# BatManagement.net
KiCad netlist of a schematic drawn in EAGLE
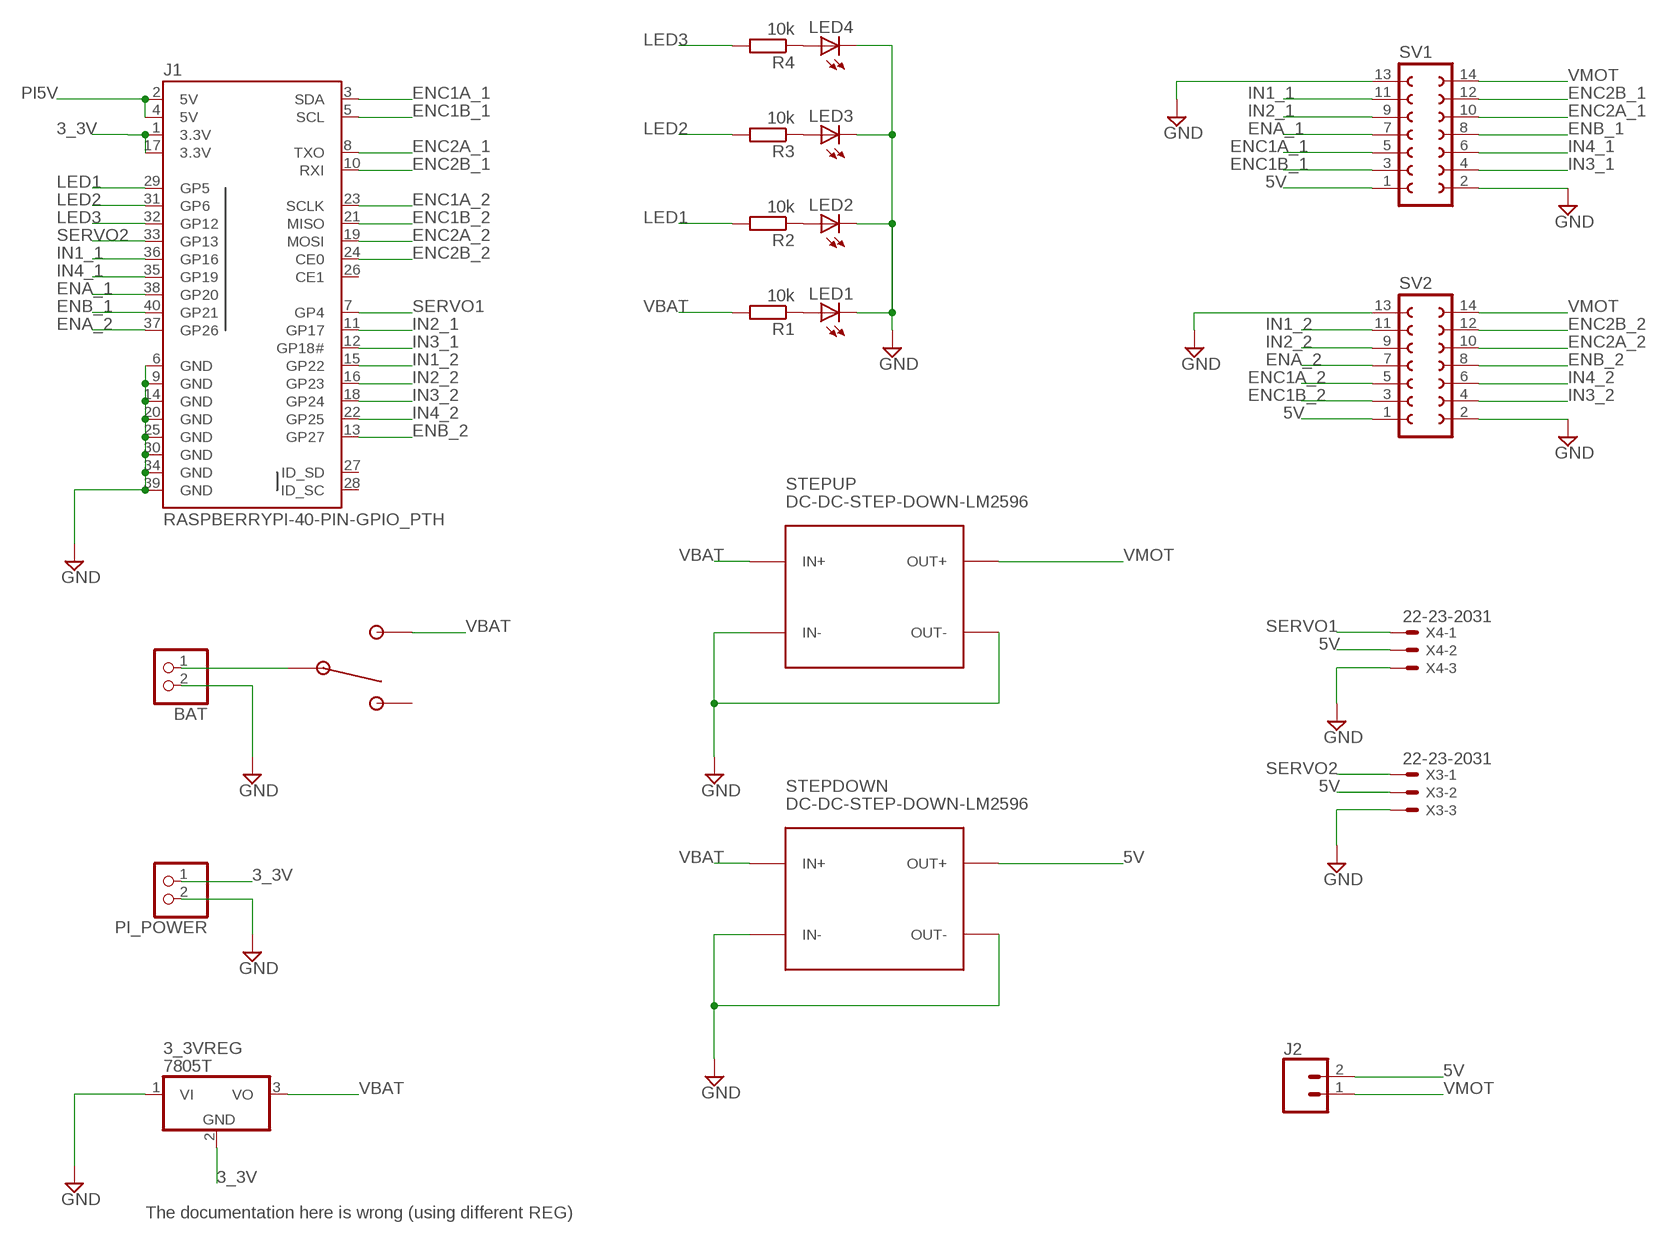
[diagram p0: schematic, sheet 1]

(export (version "E")
  (design (tool "Eeschema 10.0.6"))
  (components
    (comp (ref "3_3VREG")
      (value "7805T")
      (footprint "eagle-import:TO220H")
      (libsource (lib "eagle-import") (part "78T05"))
    )
    (comp (ref "BAT")
      (value "JST_2PIN-THM")
      (footprint "eagle-import:JST-PH-2-THM")
      (libsource (lib "eagle-import") (part "JST_2PIN-THM"))
    )
    (comp (ref "J1")
      (value "RASPBERRYPI-40-PIN-GPIO_PTH")
      (footprint "eagle-import:2X20_SHROUDED")
      (libsource (lib "eagle-import") (part "RASPBERRYPI-40-PIN-GPIO_PTH"))
    )
    (comp (ref "J2")
      (value "CONN_02")
      (footprint "eagle-import:1X02")
      (libsource (lib "eagle-import") (part "CONN_02"))
    )
    (comp (ref "LED1")
      (value "LED5MM")
      (footprint "eagle-import:LED5MM")
      (libsource (lib "eagle-import") (part "LED5MM"))
    )
    (comp (ref "LED2")
      (value "LED5MM")
      (footprint "eagle-import:LED5MM")
      (libsource (lib "eagle-import") (part "LED5MM"))
    )
    (comp (ref "LED3")
      (value "LED5MM")
      (footprint "eagle-import:LED5MM")
      (libsource (lib "eagle-import") (part "LED5MM"))
    )
    (comp (ref "LED4")
      (value "LED5MM")
      (footprint "eagle-import:LED5MM")
      (libsource (lib "eagle-import") (part "LED5MM"))
    )
    (comp (ref "PI_POWER")
      (value "JST_2PIN-THM")
      (footprint "eagle-import:JST-PH-2-THM")
      (libsource (lib "eagle-import") (part "JST_2PIN-THM"))
    )
    (comp (ref "R1")
      (value "10k")
      (footprint "eagle-import:0204_5")
      (libsource (lib "eagle-import") (part "R-EU_0204/5"))
    )
    (comp (ref "R2")
      (value "10k")
      (footprint "eagle-import:0204_5")
      (libsource (lib "eagle-import") (part "R-EU_0204/5"))
    )
    (comp (ref "R3")
      (value "10k")
      (footprint "eagle-import:0204_5")
      (libsource (lib "eagle-import") (part "R-EU_0204/5"))
    )
    (comp (ref "R4")
      (value "10k")
      (footprint "eagle-import:0204_5")
      (libsource (lib "eagle-import") (part "R-EU_0204/5"))
    )
    (comp (ref "STEPDOWN")
      (value "DC-DC-STEP-DOWN-LM2596")
      (footprint "eagle-import:DC-DC-STEP-DOWN-LM2596")
      (libsource (lib "eagle-import") (part "DC-DC-STEP-DOWN-LM2596"))
    )
    (comp (ref "STEPUP")
      (value "DC-DC-STEP-DOWN-LM2596")
      (footprint "eagle-import:DC-DC-STEP-DOWN-LM2596")
      (libsource (lib "eagle-import") (part "DC-DC-STEP-DOWN-LM2596"))
    )
    (comp (ref "SV1")
      (value "FE07-2")
      (footprint "eagle-import:FE07-2")
      (libsource (lib "eagle-import") (part "FE07-2"))
    )
    (comp (ref "SV2")
      (value "FE07-2")
      (footprint "eagle-import:FE07-2")
      (libsource (lib "eagle-import") (part "FE07-2"))
    )
    (comp (ref "SW1")
      (value "100SP1T2B4M6QE")
      (footprint "eagle-import:TOGGLE_RA")
      (fields (field (name "MF") "E-Switch"))
      (libsource (lib "eagle-import") (part "100SP1T2B4M6QE"))
    )
    (comp (ref "X3")
      (value "22-23-2031")
      (footprint "eagle-import:22-23-2031")
      (fields (field (name "MF") "MOLEX"))
      (libsource (lib "eagle-import") (part "22-23-2031"))
    )
    (comp (ref "X4")
      (value "22-23-2031")
      (footprint "eagle-import:22-23-2031")
      (fields (field (name "MF") "MOLEX"))
      (libsource (lib "eagle-import") (part "22-23-2031"))
    )
  )
  (nets
    (net (code "1") (name "/3_3V") (class "Default")
      (node (ref "3_3VREG") (pin "2") (pinfunction "GND_2") (pintype "passive"))
      (node (ref "J1") (pin "1") (pinfunction "3.3V_1") (pintype "power_in"))
      (node (ref "J1") (pin "17") (pinfunction "3.3V_17") (pintype "power_in"))
      (node (ref "PI_POWER") (pin "1") (pinfunction "2_1") (pintype "passive"))
    )
    (net (code "2") (name "/5V") (class "Default")
      (node (ref "J2") (pin "2") (pinfunction "2_2") (pintype "passive"))
      (node (ref "STEPDOWN") (pin "OUT+") (pinfunction "OUT+_OUT+") (pintype "bidirectional"))
      (node (ref "SV1") (pin "1") (pinfunction "1_1") (pintype "passive"))
      (node (ref "SV2") (pin "1") (pinfunction "1_1") (pintype "passive"))
      (node (ref "X3") (pin "2") (pinfunction "S_2") (pintype "passive"))
      (node (ref "X4") (pin "2") (pinfunction "S_2") (pintype "passive"))
    )
    (net (code "3") (name "/ENA_1") (class "Default")
      (node (ref "J1") (pin "38") (pinfunction "GP20_38") (pintype "bidirectional"))
      (node (ref "SV1") (pin "7") (pinfunction "7_7") (pintype "passive"))
    )
    (net (code "4") (name "/ENA_2") (class "Default")
      (node (ref "J1") (pin "37") (pinfunction "GP26_37") (pintype "bidirectional"))
      (node (ref "SV2") (pin "7") (pinfunction "7_7") (pintype "passive"))
    )
    (net (code "5") (name "/ENB_1") (class "Default")
      (node (ref "J1") (pin "40") (pinfunction "GP21_40") (pintype "bidirectional"))
      (node (ref "SV1") (pin "8") (pinfunction "8_8") (pintype "passive"))
    )
    (net (code "6") (name "/ENB_2") (class "Default")
      (node (ref "J1") (pin "13") (pinfunction "GP27_13") (pintype "bidirectional"))
      (node (ref "SV2") (pin "8") (pinfunction "8_8") (pintype "passive"))
    )
    (net (code "7") (name "/ENC1A_1") (class "Default")
      (node (ref "J1") (pin "3") (pinfunction "SDA_3") (pintype "bidirectional"))
      (node (ref "SV1") (pin "5") (pinfunction "5_5") (pintype "passive"))
    )
    (net (code "8") (name "/ENC1A_2") (class "Default")
      (node (ref "J1") (pin "23") (pinfunction "SCLK_23") (pintype "output"))
      (node (ref "SV2") (pin "5") (pinfunction "5_5") (pintype "passive"))
    )
    (net (code "9") (name "/ENC1B_1") (class "Default")
      (node (ref "J1") (pin "5") (pinfunction "SCL_5") (pintype "bidirectional"))
      (node (ref "SV1") (pin "3") (pinfunction "3_3") (pintype "passive"))
    )
    (net (code "10") (name "/ENC1B_2") (class "Default")
      (node (ref "J1") (pin "21") (pinfunction "MISO_21") (pintype "input"))
      (node (ref "SV2") (pin "3") (pinfunction "3_3") (pintype "passive"))
    )
    (net (code "11") (name "/ENC2A_1") (class "Default")
      (node (ref "J1") (pin "8") (pinfunction "TXO_8") (pintype "output"))
      (node (ref "SV1") (pin "10") (pinfunction "10_10") (pintype "passive"))
    )
    (net (code "12") (name "/ENC2A_2") (class "Default")
      (node (ref "J1") (pin "19") (pinfunction "MOSI_19") (pintype "output"))
      (node (ref "SV2") (pin "10") (pinfunction "10_10") (pintype "passive"))
    )
    (net (code "13") (name "/ENC2B_1") (class "Default")
      (node (ref "J1") (pin "10") (pinfunction "RXI_10") (pintype "input"))
      (node (ref "SV1") (pin "12") (pinfunction "12_12") (pintype "passive"))
    )
    (net (code "14") (name "/ENC2B_2") (class "Default")
      (node (ref "J1") (pin "24") (pinfunction "CE0_24") (pintype "output"))
      (node (ref "SV2") (pin "12") (pinfunction "12_12") (pintype "passive"))
    )
    (net (code "15") (name "/IN1_1") (class "Default")
      (node (ref "J1") (pin "36") (pinfunction "GP16_36") (pintype "bidirectional"))
      (node (ref "SV1") (pin "11") (pinfunction "11_11") (pintype "passive"))
    )
    (net (code "16") (name "/IN1_2") (class "Default")
      (node (ref "J1") (pin "15") (pinfunction "GP22_15") (pintype "bidirectional"))
      (node (ref "SV2") (pin "11") (pinfunction "11_11") (pintype "passive"))
    )
    (net (code "17") (name "/IN2_1") (class "Default")
      (node (ref "J1") (pin "11") (pinfunction "GP17_11") (pintype "bidirectional"))
      (node (ref "SV1") (pin "9") (pinfunction "9_9") (pintype "passive"))
    )
    (net (code "18") (name "/IN2_2") (class "Default")
      (node (ref "J1") (pin "16") (pinfunction "GP23_16") (pintype "bidirectional"))
      (node (ref "SV2") (pin "9") (pinfunction "9_9") (pintype "passive"))
    )
    (net (code "19") (name "/IN3_1") (class "Default")
      (node (ref "J1") (pin "12") (pinfunction "GP18#_12") (pintype "bidirectional"))
      (node (ref "SV1") (pin "4") (pinfunction "4_4") (pintype "passive"))
    )
    (net (code "20") (name "/IN3_2") (class "Default")
      (node (ref "J1") (pin "18") (pinfunction "GP24_18") (pintype "bidirectional"))
      (node (ref "SV2") (pin "4") (pinfunction "4_4") (pintype "passive"))
    )
    (net (code "21") (name "/IN4_1") (class "Default")
      (node (ref "J1") (pin "35") (pinfunction "GP19_35") (pintype "bidirectional"))
      (node (ref "SV1") (pin "6") (pinfunction "6_6") (pintype "passive"))
    )
    (net (code "22") (name "/IN4_2") (class "Default")
      (node (ref "J1") (pin "22") (pinfunction "GP25_22") (pintype "bidirectional"))
      (node (ref "SV2") (pin "6") (pinfunction "6_6") (pintype "passive"))
    )
    (net (code "23") (name "/LED1") (class "Default")
      (node (ref "J1") (pin "29") (pinfunction "GP5_29") (pintype "bidirectional"))
      (node (ref "R2") (pin "2") (pinfunction "2_2") (pintype "passive"))
    )
    (net (code "24") (name "/LED2") (class "Default")
      (node (ref "J1") (pin "31") (pinfunction "GP6_31") (pintype "bidirectional"))
      (node (ref "R3") (pin "2") (pinfunction "2_2") (pintype "passive"))
    )
    (net (code "25") (name "/LED3") (class "Default")
      (node (ref "J1") (pin "32") (pinfunction "GP12_32") (pintype "bidirectional"))
      (node (ref "R4") (pin "2") (pinfunction "2_2") (pintype "passive"))
    )
    (net (code "26") (name "/PI5V") (class "Default")
      (node (ref "J1") (pin "2") (pinfunction "5V_2") (pintype "power_in"))
      (node (ref "J1") (pin "4") (pinfunction "5V_4") (pintype "power_in"))
    )
    (net (code "27") (name "/SERVO1") (class "Default")
      (node (ref "J1") (pin "7") (pinfunction "GP4_7") (pintype "bidirectional"))
      (node (ref "X4") (pin "1") (pinfunction "S_1") (pintype "passive"))
    )
    (net (code "28") (name "/SERVO2") (class "Default")
      (node (ref "J1") (pin "33") (pinfunction "GP13_33") (pintype "bidirectional"))
      (node (ref "X3") (pin "1") (pinfunction "S_1") (pintype "passive"))
    )
    (net (code "29") (name "/VBAT") (class "Default")
      (node (ref "3_3VREG") (pin "3") (pinfunction "VO_3") (pintype "passive"))
      (node (ref "R1") (pin "2") (pinfunction "2_2") (pintype "passive"))
      (node (ref "STEPDOWN") (pin "IN+") (pinfunction "IN+_IN+") (pintype "bidirectional"))
      (node (ref "STEPUP") (pin "IN+") (pinfunction "IN+_IN+") (pintype "bidirectional"))
      (node (ref "SW1") (pin "1") (pinfunction "P$2_1") (pintype "bidirectional"))
    )
    (net (code "30") (name "/VMOT") (class "Default")
      (node (ref "J2") (pin "1") (pinfunction "1_1") (pintype "passive"))
      (node (ref "STEPUP") (pin "OUT+") (pinfunction "OUT+_OUT+") (pintype "bidirectional"))
      (node (ref "SV1") (pin "14") (pinfunction "14_14") (pintype "passive"))
      (node (ref "SV2") (pin "14") (pinfunction "14_14") (pintype "passive"))
    )
    (net (code "31") (name "GND") (class "Default")
      (node (ref "3_3VREG") (pin "1") (pinfunction "VI_1") (pintype "input"))
      (node (ref "BAT") (pin "2") (pinfunction "1_2") (pintype "passive"))
      (node (ref "J1") (pin "14") (pinfunction "GND_14") (pintype "power_in"))
      (node (ref "J1") (pin "20") (pinfunction "GND_20") (pintype "power_in"))
      (node (ref "J1") (pin "25") (pinfunction "GND_25") (pintype "power_in"))
      (node (ref "J1") (pin "30") (pinfunction "GND_30") (pintype "power_in"))
      (node (ref "J1") (pin "34") (pinfunction "GND_34") (pintype "power_in"))
      (node (ref "J1") (pin "39") (pinfunction "GND_39") (pintype "power_in"))
      (node (ref "J1") (pin "6") (pinfunction "GND_6") (pintype "power_in"))
      (node (ref "J1") (pin "9") (pinfunction "GND_9") (pintype "power_in"))
      (node (ref "LED1") (pin "K") (pinfunction "C_K") (pintype "passive"))
      (node (ref "LED2") (pin "K") (pinfunction "C_K") (pintype "passive"))
      (node (ref "LED3") (pin "K") (pinfunction "C_K") (pintype "passive"))
      (node (ref "LED4") (pin "K") (pinfunction "C_K") (pintype "passive"))
      (node (ref "PI_POWER") (pin "2") (pinfunction "1_2") (pintype "passive"))
      (node (ref "STEPDOWN") (pin "IN-") (pinfunction "IN-_IN-") (pintype "bidirectional"))
      (node (ref "STEPDOWN") (pin "OUT-") (pinfunction "OUT-_OUT-") (pintype "bidirectional"))
      (node (ref "STEPUP") (pin "IN-") (pinfunction "IN-_IN-") (pintype "bidirectional"))
      (node (ref "STEPUP") (pin "OUT-") (pinfunction "OUT-_OUT-") (pintype "bidirectional"))
      (node (ref "SV1") (pin "13") (pinfunction "13_13") (pintype "passive"))
      (node (ref "SV1") (pin "2") (pinfunction "2_2") (pintype "passive"))
      (node (ref "SV2") (pin "13") (pinfunction "13_13") (pintype "passive"))
      (node (ref "SV2") (pin "2") (pinfunction "2_2") (pintype "passive"))
      (node (ref "X3") (pin "3") (pinfunction "S_3") (pintype "passive"))
      (node (ref "X4") (pin "3") (pinfunction "S_3") (pintype "passive"))
    )
    (net (code "32") (name "Net-(BAT-2)") (class "Default")
      (node (ref "BAT") (pin "1") (pinfunction "2_1") (pintype "passive"))
      (node (ref "SW1") (pin "2") (pinfunction "COM_2") (pintype "bidirectional"))
    )
    (net (code "33") (name "Net-(LED1-PadA)") (class "Default")
      (node (ref "LED1") (pin "A") (pinfunction "A_A") (pintype "passive"))
      (node (ref "R1") (pin "1") (pinfunction "1_1") (pintype "passive"))
    )
    (net (code "34") (name "Net-(LED2-PadA)") (class "Default")
      (node (ref "LED2") (pin "A") (pinfunction "A_A") (pintype "passive"))
      (node (ref "R2") (pin "1") (pinfunction "1_1") (pintype "passive"))
    )
    (net (code "35") (name "Net-(LED3-PadA)") (class "Default")
      (node (ref "LED3") (pin "A") (pinfunction "A_A") (pintype "passive"))
      (node (ref "R3") (pin "1") (pinfunction "1_1") (pintype "passive"))
    )
    (net (code "36") (name "Net-(LED4-PadA)") (class "Default")
      (node (ref "LED4") (pin "A") (pinfunction "A_A") (pintype "passive"))
      (node (ref "R4") (pin "1") (pinfunction "1_1") (pintype "passive"))
    )
    (net (code "37") (name "unconnected-(J1-CE1-Pad26)") (class "Default")
      (node (ref "J1") (pin "26") (pinfunction "CE1_26") (pintype "output"))
    )
    (net (code "38") (name "unconnected-(J1-ID_SC-Pad28)") (class "Default")
      (node (ref "J1") (pin "28") (pinfunction "ID_SC_28") (pintype "bidirectional"))
    )
    (net (code "39") (name "unconnected-(J1-ID_SD-Pad27)") (class "Default")
      (node (ref "J1") (pin "27") (pinfunction "ID_SD_27") (pintype "bidirectional"))
    )
    (net (code "40") (name "unconnected-(SW1-P$3-Pad3)") (class "Default")
      (node (ref "SW1") (pin "3") (pinfunction "P$3_3") (pintype "bidirectional"))
    )
  )
)
